# InverterConnector.net
KiCad netlist of a schematic drawn in Altium Designer
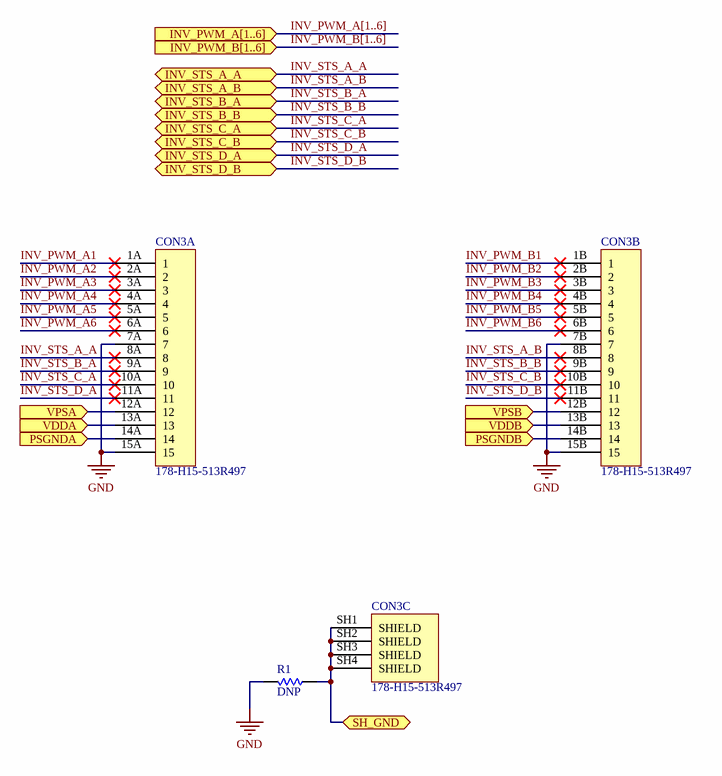
[diagram p0: InverterConnector.SchDoc]

(export (version "E")
  (design (tool "Eeschema 10.0.6"))
  (components
    (comp (ref "CON3")
      (value "178-H15-513R497")
      (footprint "AMDC:178-H15-513R497")
      (description "CONN D-SUB RCPT/RCPT 15/15POS RA")
      (libsource (lib "AMDC") (part "178-H15-513R497"))
    )
    (comp (ref "R1")
      (value "DNP")
      (footprint "AMDC:0603-RES")
      (description "Resistor")
      (libsource (lib "AMDC") (part "Resistor"))
    )
  )
  (nets
    (net (code "1") (name "/INV_PWM_A1") (class "Default")
      (node (ref "CON3") (pin "1A") (pinfunction "1_1A") (pintype "passive+no_connect"))
    )
    (net (code "2") (name "/INV_PWM_A2") (class "Default")
      (node (ref "CON3") (pin "2A") (pinfunction "2_2A") (pintype "passive+no_connect"))
    )
    (net (code "3") (name "/INV_PWM_A3") (class "Default")
      (node (ref "CON3") (pin "3A") (pinfunction "3_3A") (pintype "passive+no_connect"))
    )
    (net (code "4") (name "/INV_PWM_A4") (class "Default")
      (node (ref "CON3") (pin "4A") (pinfunction "4_4A") (pintype "passive+no_connect"))
    )
    (net (code "5") (name "/INV_PWM_A5") (class "Default")
      (node (ref "CON3") (pin "5A") (pinfunction "5_5A") (pintype "passive+no_connect"))
    )
    (net (code "6") (name "/INV_PWM_A6") (class "Default")
      (node (ref "CON3") (pin "6A") (pinfunction "6_6A") (pintype "passive+no_connect"))
    )
    (net (code "8") (name "/INV_PWM_B1") (class "Default")
      (node (ref "CON3") (pin "1B") (pinfunction "1_1B") (pintype "passive+no_connect"))
    )
    (net (code "9") (name "/INV_PWM_B2") (class "Default")
      (node (ref "CON3") (pin "2B") (pinfunction "2_2B") (pintype "passive+no_connect"))
    )
    (net (code "10") (name "/INV_PWM_B3") (class "Default")
      (node (ref "CON3") (pin "3B") (pinfunction "3_3B") (pintype "passive+no_connect"))
    )
    (net (code "11") (name "/INV_PWM_B4") (class "Default")
      (node (ref "CON3") (pin "4B") (pinfunction "4_4B") (pintype "passive+no_connect"))
    )
    (net (code "12") (name "/INV_PWM_B5") (class "Default")
      (node (ref "CON3") (pin "5B") (pinfunction "5_5B") (pintype "passive+no_connect"))
    )
    (net (code "13") (name "/INV_PWM_B6") (class "Default")
      (node (ref "CON3") (pin "6B") (pinfunction "6_6B") (pintype "passive+no_connect"))
    )
    (net (code "15") (name "/INV_STS_A_A") (class "Default")
      (node (ref "CON3") (pin "8A") (pinfunction "8_8A") (pintype "passive+no_connect"))
    )
    (net (code "16") (name "/INV_STS_A_B") (class "Default")
      (node (ref "CON3") (pin "8B") (pinfunction "8_8B") (pintype "passive+no_connect"))
    )
    (net (code "17") (name "/INV_STS_B_A") (class "Default")
      (node (ref "CON3") (pin "9A") (pinfunction "9_9A") (pintype "passive+no_connect"))
    )
    (net (code "18") (name "/INV_STS_B_B") (class "Default")
      (node (ref "CON3") (pin "9B") (pinfunction "9_9B") (pintype "passive+no_connect"))
    )
    (net (code "19") (name "/INV_STS_C_A") (class "Default")
      (node (ref "CON3") (pin "10A") (pinfunction "10_10A") (pintype "passive+no_connect"))
    )
    (net (code "20") (name "/INV_STS_C_B") (class "Default")
      (node (ref "CON3") (pin "10B") (pinfunction "10_10B") (pintype "passive+no_connect"))
    )
    (net (code "21") (name "/INV_STS_D_A") (class "Default")
      (node (ref "CON3") (pin "11A") (pinfunction "11_11A") (pintype "passive+no_connect"))
    )
    (net (code "22") (name "/INV_STS_D_B") (class "Default")
      (node (ref "CON3") (pin "11B") (pinfunction "11_11B") (pintype "passive+no_connect"))
    )
    (net (code "23") (name "/PSGNDA") (class "Default")
      (node (ref "CON3") (pin "14A") (pinfunction "14_14A") (pintype "passive"))
    )
    (net (code "24") (name "/PSGNDB") (class "Default")
      (node (ref "CON3") (pin "14B") (pinfunction "14_14B") (pintype "passive"))
    )
    (net (code "25") (name "/SH_GND") (class "Default")
      (node (ref "CON3") (pin "SH1") (pinfunction "SHIELD_SH1") (pintype "passive"))
      (node (ref "CON3") (pin "SH2") (pinfunction "SHIELD_SH2") (pintype "passive"))
      (node (ref "CON3") (pin "SH3") (pinfunction "SHIELD_SH3") (pintype "passive"))
      (node (ref "CON3") (pin "SH4") (pinfunction "SHIELD_SH4") (pintype "passive"))
      (node (ref "R1") (pin "1") (pinfunction "1_1") (pintype "passive"))
    )
    (net (code "26") (name "/VDDA") (class "Default")
      (node (ref "CON3") (pin "13A") (pinfunction "13_13A") (pintype "passive"))
    )
    (net (code "27") (name "/VDDB") (class "Default")
      (node (ref "CON3") (pin "13B") (pinfunction "13_13B") (pintype "passive"))
    )
    (net (code "28") (name "/VPSA") (class "Default")
      (node (ref "CON3") (pin "12A") (pinfunction "12_12A") (pintype "passive"))
    )
    (net (code "29") (name "/VPSB") (class "Default")
      (node (ref "CON3") (pin "12B") (pinfunction "12_12B") (pintype "passive"))
    )
    (net (code "30") (name "GND") (class "Default")
      (node (ref "CON3") (pin "15A") (pinfunction "15_15A") (pintype "passive"))
      (node (ref "CON3") (pin "15B") (pinfunction "15_15B") (pintype "passive"))
      (node (ref "CON3") (pin "7A") (pinfunction "7_7A") (pintype "passive"))
      (node (ref "CON3") (pin "7B") (pinfunction "7_7B") (pintype "passive"))
      (node (ref "R1") (pin "2") (pinfunction "2_2") (pintype "passive"))
    )
  )
)
